# Open_IR_Blaster.net
KiCad netlist of a schematic drawn in EAGLE
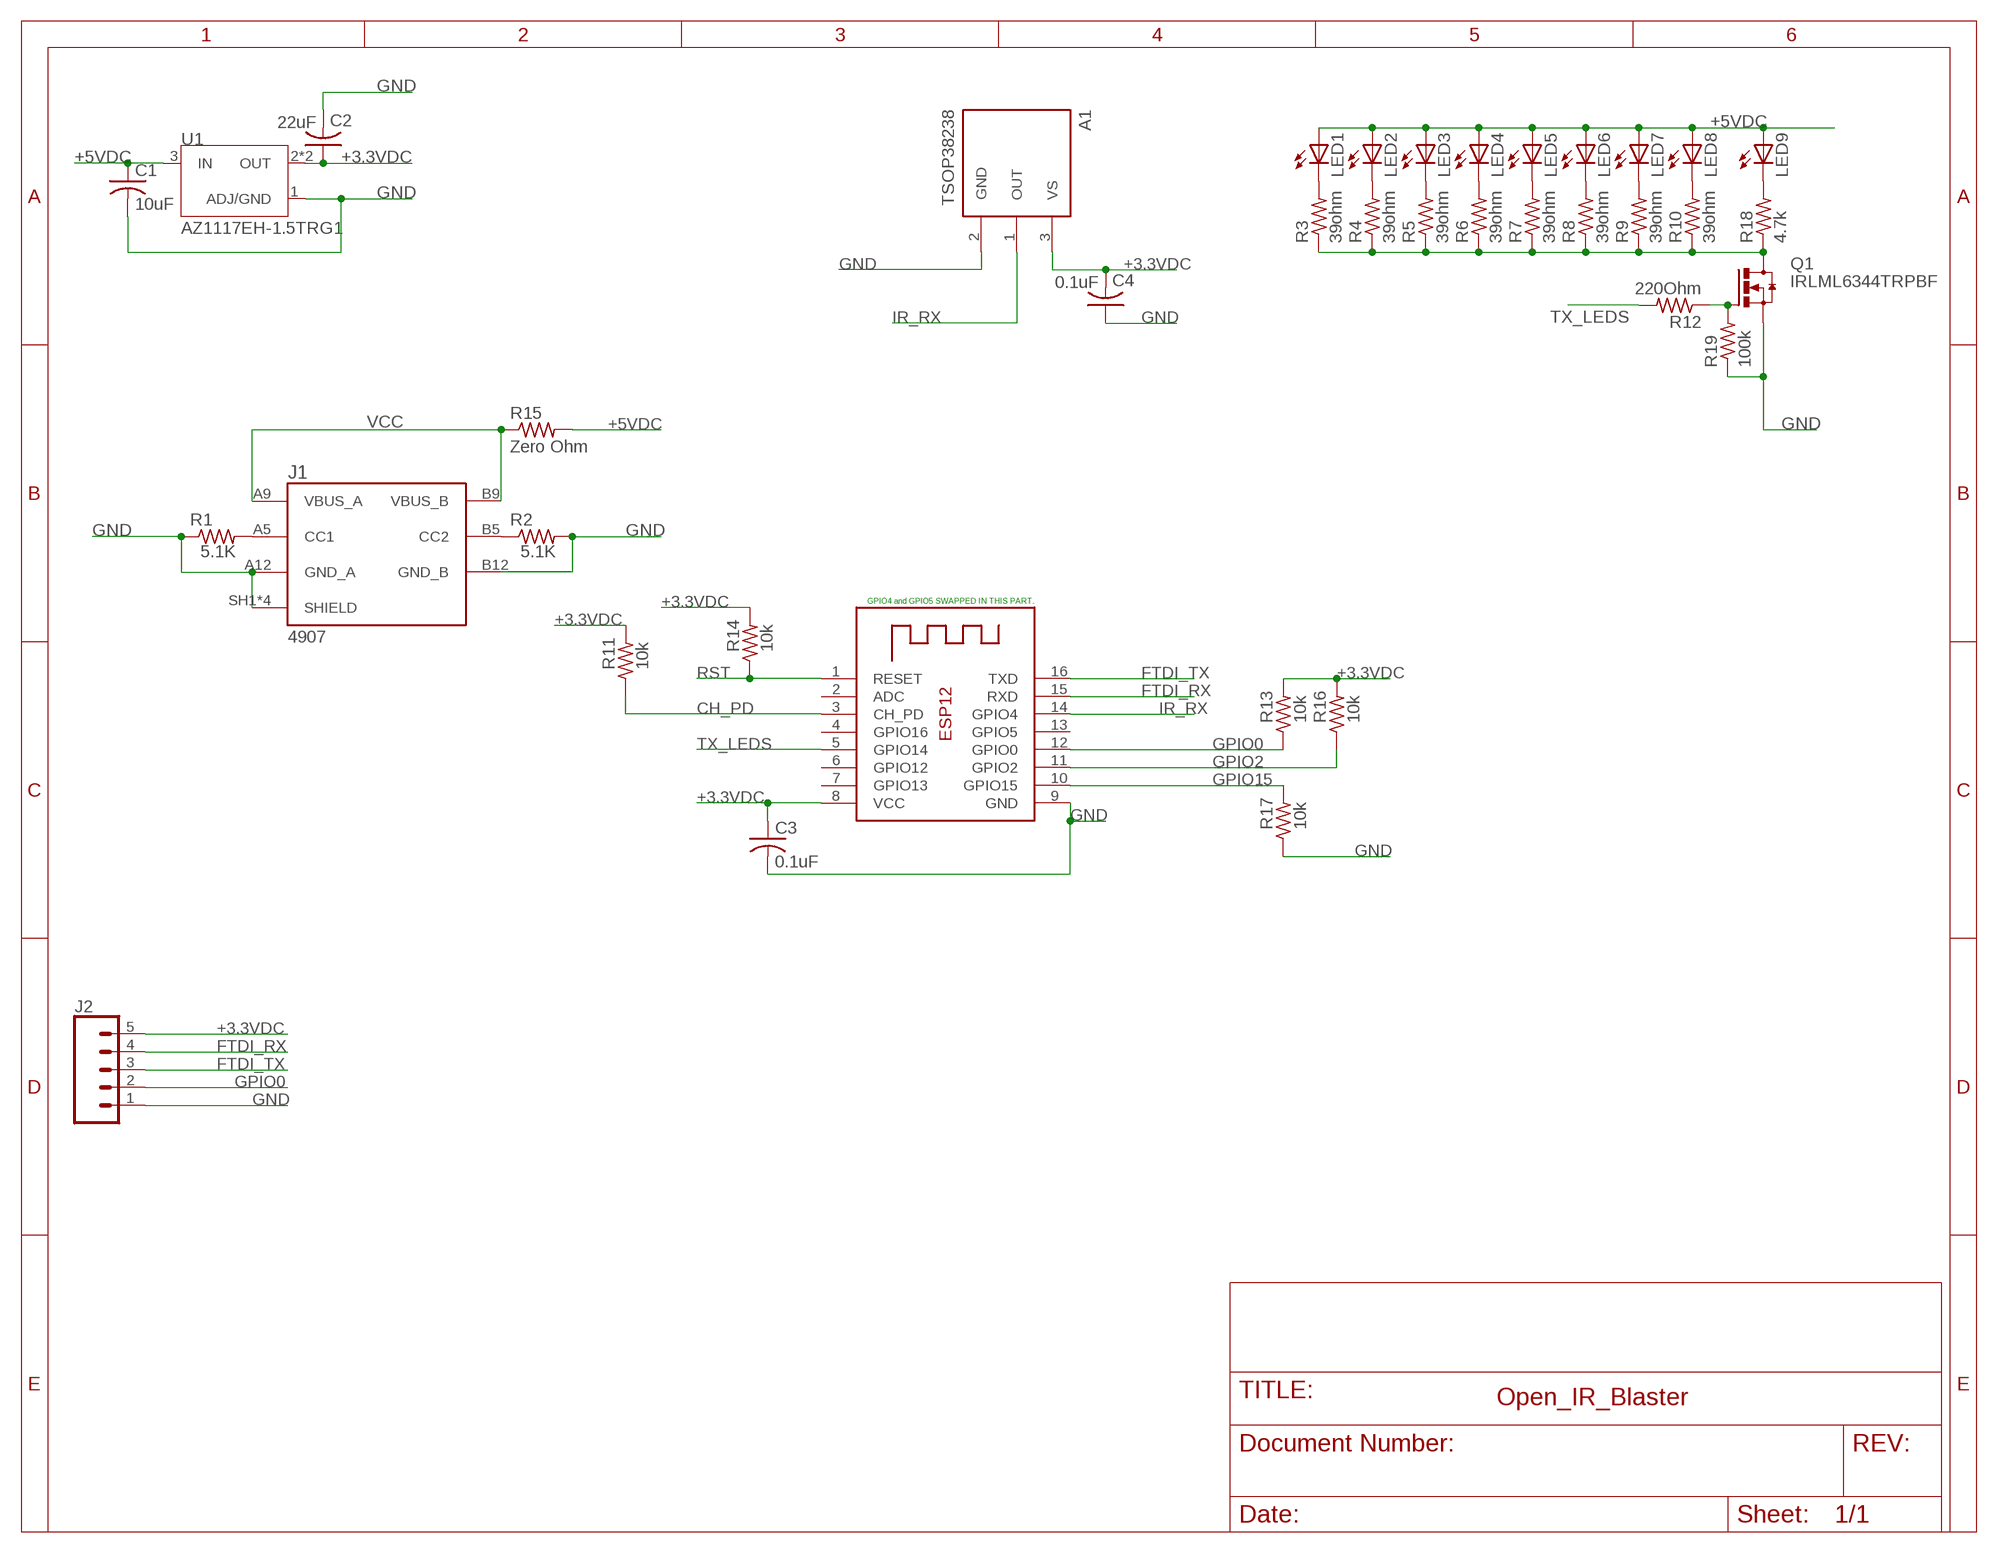
[diagram p0: schematic, sheet 1]

(export (version "E")
  (design (tool "Eeschema 10.0.6"))
  (components
    (comp (ref "A1")
      (value "TSOP38238")
      (footprint "eagle-import:XDCR_TSOP38238")
      (fields (field (name "DIGIKEY_PART_NUMBER") "751-1227-ND") (field (name "MF") "Vishay"))
      (libsource (lib "eagle-import") (part "TSOP38238"))
    )
    (comp (ref "C1")
      (value "10uF")
      (footprint "eagle-import:C0805")
      (libsource (lib "eagle-import") (part "C-USC0805"))
    )
    (comp (ref "C2")
      (value "22uF")
      (footprint "eagle-import:C0805")
      (libsource (lib "eagle-import") (part "C-USC0805"))
    )
    (comp (ref "C3")
      (value "0.1uF")
      (footprint "eagle-import:C0805")
      (libsource (lib "eagle-import") (part "C-USC0805"))
    )
    (comp (ref "C4")
      (value "0.1uF")
      (footprint "eagle-import:C0805")
      (libsource (lib "eagle-import") (part "C-USC0805"))
    )
    (comp (ref "J1")
      (value "4907")
      (footprint "eagle-import:ADAFRUIT_4907")
      (fields (field (name "MF") "Adafruit Industries LLC"))
      (libsource (lib "eagle-import") (part "4907"))
    )
    (comp (ref "J2")
      (value "CONN_05PTH_LONGPADS")
      (footprint "eagle-import:1X05_LONGPADS")
      (libsource (lib "eagle-import") (part "CONN_05PTH_LONGPADS"))
    )
    (comp (ref "LED1")
      (value "LED5MM")
      (footprint "eagle-import:LED5MM")
      (libsource (lib "eagle-import") (part "LED5MM"))
    )
    (comp (ref "LED2")
      (value "LED5MM")
      (footprint "eagle-import:LED5MM")
      (libsource (lib "eagle-import") (part "LED5MM"))
    )
    (comp (ref "LED3")
      (value "LED5MM")
      (footprint "eagle-import:LED5MM")
      (libsource (lib "eagle-import") (part "LED5MM"))
    )
    (comp (ref "LED4")
      (value "LED5MM")
      (footprint "eagle-import:LED5MM")
      (libsource (lib "eagle-import") (part "LED5MM"))
    )
    (comp (ref "LED5")
      (value "LED5MM")
      (footprint "eagle-import:LED5MM")
      (libsource (lib "eagle-import") (part "LED5MM"))
    )
    (comp (ref "LED6")
      (value "LED5MM")
      (footprint "eagle-import:LED5MM")
      (libsource (lib "eagle-import") (part "LED5MM"))
    )
    (comp (ref "LED7")
      (value "LED5MM")
      (footprint "eagle-import:LED5MM")
      (libsource (lib "eagle-import") (part "LED5MM"))
    )
    (comp (ref "LED8")
      (value "LED5MM")
      (footprint "eagle-import:LED5MM")
      (libsource (lib "eagle-import") (part "LED5MM"))
    )
    (comp (ref "LED9")
      (value "LEDCHIP-LED0603")
      (footprint "eagle-import:CHIP-LED0603")
      (libsource (lib "eagle-import") (part "LEDCHIP-LED0603"))
    )
    (comp (ref "Q1")
      (value "IRLML6344TRPBF")
      (footprint "eagle-import:SOT23")
      (fields
        (field (name "DIGIKEY_PART_NUMBER") "IRLML6344TRPBFTR-ND")
        (field (name "MF") "Infineon Technologies")
      )
      (libsource (lib "eagle-import") (part "IRLML6344TRPBF"))
    )
    (comp (ref "R1")
      (value "5.1K")
      (footprint "eagle-import:M0805")
      (libsource (lib "eagle-import") (part "R-US_M0805"))
    )
    (comp (ref "R2")
      (value "5.1K")
      (footprint "eagle-import:M0805")
      (libsource (lib "eagle-import") (part "R-US_M0805"))
    )
    (comp (ref "R3")
      (value "39ohm")
      (footprint "eagle-import:R1210")
      (libsource (lib "eagle-import") (part "R-US_R1210"))
    )
    (comp (ref "R4")
      (value "39ohm")
      (footprint "eagle-import:R1210")
      (libsource (lib "eagle-import") (part "R-US_R1210"))
    )
    (comp (ref "R5")
      (value "39ohm")
      (footprint "eagle-import:R1210")
      (libsource (lib "eagle-import") (part "R-US_R1210"))
    )
    (comp (ref "R6")
      (value "39ohm")
      (footprint "eagle-import:R1210")
      (libsource (lib "eagle-import") (part "R-US_R1210"))
    )
    (comp (ref "R7")
      (value "39ohm")
      (footprint "eagle-import:R1210")
      (libsource (lib "eagle-import") (part "R-US_R1210"))
    )
    (comp (ref "R8")
      (value "39ohm")
      (footprint "eagle-import:R1210")
      (libsource (lib "eagle-import") (part "R-US_R1210"))
    )
    (comp (ref "R9")
      (value "39ohm")
      (footprint "eagle-import:R1210")
      (libsource (lib "eagle-import") (part "R-US_R1210"))
    )
    (comp (ref "R10")
      (value "39ohm")
      (footprint "eagle-import:R1210")
      (libsource (lib "eagle-import") (part "R-US_R1210"))
    )
    (comp (ref "R11")
      (value "10k")
      (footprint "eagle-import:M0805")
      (libsource (lib "eagle-import") (part "R-US_M0805"))
    )
    (comp (ref "R12")
      (value "220Ohm")
      (footprint "eagle-import:M0805")
      (libsource (lib "eagle-import") (part "R-US_M0805"))
    )
    (comp (ref "R13")
      (value "10k")
      (footprint "eagle-import:M0805")
      (libsource (lib "eagle-import") (part "R-US_M0805"))
    )
    (comp (ref "R14")
      (value "10k")
      (footprint "eagle-import:M0805")
      (libsource (lib "eagle-import") (part "R-US_M0805"))
    )
    (comp (ref "R15")
      (value "Zero Ohm")
      (footprint "eagle-import:R1210")
      (libsource (lib "eagle-import") (part "adafruit_420_R-US_R1210"))
    )
    (comp (ref "R16")
      (value "10k")
      (footprint "eagle-import:M0805")
      (libsource (lib "eagle-import") (part "R-US_M0805"))
    )
    (comp (ref "R17")
      (value "10k")
      (footprint "eagle-import:M0805")
      (libsource (lib "eagle-import") (part "R-US_M0805"))
    )
    (comp (ref "R18")
      (value "4.7k")
      (footprint "eagle-import:R0603")
      (libsource (lib "eagle-import") (part "adafruit_420_R-US_R0603"))
    )
    (comp (ref "R19")
      (value "100k")
      (footprint "eagle-import:R0603")
      (libsource (lib "eagle-import") (part "adafruit_420_R-US_R0603"))
    )
    (comp (ref "U1")
      (value "AZ1117EH-1.5TRG1")
      (footprint "eagle-import:SOT230P700X180-4N")
      (fields (field (name "MF") "Diodes Inc."))
      (libsource (lib "eagle-import") (part "AZ1117EH-1.5TRG1"))
    )
    (comp (ref "X1")
      (value "ESP-12")
      (footprint "eagle-import:ESP-12")
      (libsource (lib "eagle-import") (part "ESP-12"))
    )
  )
  (nets
    (net (code "1") (name "/+3.3VDC") (class "Default")
      (node (ref "A1") (pin "3") (pinfunction "VS_3") (pintype "power_in"))
      (node (ref "C2") (pin "1") (pinfunction "1_1") (pintype "passive"))
      (node (ref "C3") (pin "1") (pinfunction "1_1") (pintype "passive"))
      (node (ref "C4") (pin "2") (pinfunction "2_2") (pintype "passive"))
      (node (ref "J2") (pin "5") (pinfunction "5_5") (pintype "passive"))
      (node (ref "R11") (pin "2") (pinfunction "2_2") (pintype "passive"))
      (node (ref "R13") (pin "2") (pinfunction "2_2") (pintype "passive"))
      (node (ref "R14") (pin "2") (pinfunction "2_2") (pintype "passive"))
      (node (ref "R16") (pin "2") (pinfunction "2_2") (pintype "passive"))
      (node (ref "U1") (pin "2") (pinfunction "OUT_2") (pintype "output"))
      (node (ref "U1") (pin "4") (pinfunction "OUT_4") (pintype "output"))
      (node (ref "X1") (pin "8") (pinfunction "VCC_8") (pintype "power_in"))
    )
    (net (code "2") (name "/+5VDC") (class "Default")
      (node (ref "C1") (pin "1") (pinfunction "1_1") (pintype "passive"))
      (node (ref "LED1") (pin "A") (pinfunction "A_A") (pintype "passive"))
      (node (ref "LED2") (pin "A") (pinfunction "A_A") (pintype "passive"))
      (node (ref "LED3") (pin "A") (pinfunction "A_A") (pintype "passive"))
      (node (ref "LED4") (pin "A") (pinfunction "A_A") (pintype "passive"))
      (node (ref "LED5") (pin "A") (pinfunction "A_A") (pintype "passive"))
      (node (ref "LED6") (pin "A") (pinfunction "A_A") (pintype "passive"))
      (node (ref "LED7") (pin "A") (pinfunction "A_A") (pintype "passive"))
      (node (ref "LED8") (pin "A") (pinfunction "A_A") (pintype "passive"))
      (node (ref "LED9") (pin "A") (pinfunction "A_A") (pintype "passive"))
      (node (ref "R15") (pin "2") (pinfunction "2_2") (pintype "passive"))
      (node (ref "U1") (pin "3") (pinfunction "IN_3") (pintype "input"))
    )
    (net (code "3") (name "/CH_PD") (class "Default")
      (node (ref "R11") (pin "1") (pinfunction "1_1") (pintype "passive"))
      (node (ref "X1") (pin "3") (pinfunction "CH_PD_3") (pintype "input"))
    )
    (net (code "4") (name "/FTDI_RX") (class "Default")
      (node (ref "J2") (pin "4") (pinfunction "4_4") (pintype "passive"))
      (node (ref "X1") (pin "15") (pinfunction "RXD_15") (pintype "input"))
    )
    (net (code "5") (name "/FTDI_TX") (class "Default")
      (node (ref "J2") (pin "3") (pinfunction "3_3") (pintype "passive"))
      (node (ref "X1") (pin "16") (pinfunction "TXD_16") (pintype "output"))
    )
    (net (code "6") (name "/GND") (class "Default")
      (node (ref "A1") (pin "2") (pinfunction "GND_2") (pintype "power_in"))
      (node (ref "C1") (pin "2") (pinfunction "2_2") (pintype "passive"))
      (node (ref "C2") (pin "2") (pinfunction "2_2") (pintype "passive"))
      (node (ref "C3") (pin "2") (pinfunction "2_2") (pintype "passive"))
      (node (ref "C4") (pin "1") (pinfunction "1_1") (pintype "passive"))
      (node (ref "J1") (pin "A12") (pinfunction "GND_A_A12") (pintype "power_in"))
      (node (ref "J1") (pin "B12") (pinfunction "GND_B_B12") (pintype "power_in"))
      (node (ref "J1") (pin "SH1") (pinfunction "SHIELD_SH1") (pintype "passive"))
      (node (ref "J1") (pin "SH2") (pinfunction "SHIELD_SH2") (pintype "passive"))
      (node (ref "J1") (pin "SH3") (pinfunction "SHIELD_SH3") (pintype "passive"))
      (node (ref "J1") (pin "SH4") (pinfunction "SHIELD_SH4") (pintype "passive"))
      (node (ref "J2") (pin "1") (pinfunction "1_1") (pintype "passive"))
      (node (ref "Q1") (pin "2") (pinfunction "S_2") (pintype "passive"))
      (node (ref "R1") (pin "1") (pinfunction "1_1") (pintype "passive"))
      (node (ref "R17") (pin "1") (pinfunction "1_1") (pintype "passive"))
      (node (ref "R19") (pin "1") (pinfunction "1_1") (pintype "passive"))
      (node (ref "R2") (pin "2") (pinfunction "2_2") (pintype "passive"))
      (node (ref "U1") (pin "1") (pinfunction "ADJ/GND_1") (pintype "power_in"))
      (node (ref "X1") (pin "9") (pinfunction "GND_9") (pintype "power_in"))
    )
    (net (code "7") (name "/GPIO0") (class "Default")
      (node (ref "J2") (pin "2") (pinfunction "2_2") (pintype "passive"))
      (node (ref "R13") (pin "1") (pinfunction "1_1") (pintype "passive"))
      (node (ref "X1") (pin "12") (pinfunction "GPIO0_12") (pintype "bidirectional"))
    )
    (net (code "8") (name "/GPIO2") (class "Default")
      (node (ref "R16") (pin "1") (pinfunction "1_1") (pintype "passive"))
      (node (ref "X1") (pin "11") (pinfunction "GPIO2_11") (pintype "bidirectional"))
    )
    (net (code "9") (name "/GPIO15") (class "Default")
      (node (ref "R17") (pin "2") (pinfunction "2_2") (pintype "passive"))
      (node (ref "X1") (pin "10") (pinfunction "GPIO15_10") (pintype "bidirectional"))
    )
    (net (code "10") (name "/IR_RX") (class "Default")
      (node (ref "A1") (pin "1") (pinfunction "OUT_1") (pintype "output"))
      (node (ref "X1") (pin "14") (pinfunction "GPIO4_14") (pintype "bidirectional"))
    )
    (net (code "11") (name "/RST") (class "Default")
      (node (ref "R14") (pin "1") (pinfunction "1_1") (pintype "passive"))
      (node (ref "X1") (pin "1") (pinfunction "RESET_1") (pintype "input"))
    )
    (net (code "12") (name "/TX_LEDS") (class "Default")
      (node (ref "R12") (pin "2") (pinfunction "2_2") (pintype "passive"))
      (node (ref "X1") (pin "5") (pinfunction "GPIO14_5") (pintype "bidirectional"))
    )
    (net (code "13") (name "/VCC") (class "Default")
      (node (ref "J1") (pin "A9") (pinfunction "VBUS_A_A9") (pintype "power_in"))
      (node (ref "J1") (pin "B9") (pinfunction "VBUS_B_B9") (pintype "power_in"))
      (node (ref "R15") (pin "1") (pinfunction "1_1") (pintype "passive"))
    )
    (net (code "14") (name "Net-(J1-CC1)") (class "Default")
      (node (ref "J1") (pin "A5") (pinfunction "CC1_A5") (pintype "bidirectional"))
      (node (ref "R1") (pin "2") (pinfunction "2_2") (pintype "passive"))
    )
    (net (code "15") (name "Net-(J1-CC2)") (class "Default")
      (node (ref "J1") (pin "B5") (pinfunction "CC2_B5") (pintype "bidirectional"))
      (node (ref "R2") (pin "1") (pinfunction "1_1") (pintype "passive"))
    )
    (net (code "16") (name "Net-(LED1-C)") (class "Default")
      (node (ref "LED1") (pin "K") (pinfunction "C_K") (pintype "passive"))
      (node (ref "R3") (pin "2") (pinfunction "2_2") (pintype "passive"))
    )
    (net (code "17") (name "Net-(LED2-C)") (class "Default")
      (node (ref "LED2") (pin "K") (pinfunction "C_K") (pintype "passive"))
      (node (ref "R4") (pin "2") (pinfunction "2_2") (pintype "passive"))
    )
    (net (code "18") (name "Net-(LED3-C)") (class "Default")
      (node (ref "LED3") (pin "K") (pinfunction "C_K") (pintype "passive"))
      (node (ref "R5") (pin "2") (pinfunction "2_2") (pintype "passive"))
    )
    (net (code "19") (name "Net-(LED4-C)") (class "Default")
      (node (ref "LED4") (pin "K") (pinfunction "C_K") (pintype "passive"))
      (node (ref "R6") (pin "2") (pinfunction "2_2") (pintype "passive"))
    )
    (net (code "20") (name "Net-(LED5-C)") (class "Default")
      (node (ref "LED5") (pin "K") (pinfunction "C_K") (pintype "passive"))
      (node (ref "R7") (pin "2") (pinfunction "2_2") (pintype "passive"))
    )
    (net (code "21") (name "Net-(LED6-C)") (class "Default")
      (node (ref "LED6") (pin "K") (pinfunction "C_K") (pintype "passive"))
      (node (ref "R8") (pin "2") (pinfunction "2_2") (pintype "passive"))
    )
    (net (code "22") (name "Net-(LED7-C)") (class "Default")
      (node (ref "LED7") (pin "K") (pinfunction "C_K") (pintype "passive"))
      (node (ref "R9") (pin "2") (pinfunction "2_2") (pintype "passive"))
    )
    (net (code "23") (name "Net-(LED8-C)") (class "Default")
      (node (ref "LED8") (pin "K") (pinfunction "C_K") (pintype "passive"))
      (node (ref "R10") (pin "2") (pinfunction "2_2") (pintype "passive"))
    )
    (net (code "24") (name "Net-(LED9-PadC)") (class "Default")
      (node (ref "LED9") (pin "C") (pinfunction "C_C") (pintype "passive"))
      (node (ref "R18") (pin "2") (pinfunction "2_2") (pintype "passive"))
    )
    (net (code "25") (name "Net-(Q1-D)") (class "Default")
      (node (ref "Q1") (pin "3") (pinfunction "D_3") (pintype "passive"))
      (node (ref "R10") (pin "1") (pinfunction "1_1") (pintype "passive"))
      (node (ref "R18") (pin "1") (pinfunction "1_1") (pintype "passive"))
      (node (ref "R3") (pin "1") (pinfunction "1_1") (pintype "passive"))
      (node (ref "R4") (pin "1") (pinfunction "1_1") (pintype "passive"))
      (node (ref "R5") (pin "1") (pinfunction "1_1") (pintype "passive"))
      (node (ref "R6") (pin "1") (pinfunction "1_1") (pintype "passive"))
      (node (ref "R7") (pin "1") (pinfunction "1_1") (pintype "passive"))
      (node (ref "R8") (pin "1") (pinfunction "1_1") (pintype "passive"))
      (node (ref "R9") (pin "1") (pinfunction "1_1") (pintype "passive"))
    )
    (net (code "26") (name "Net-(Q1-G)") (class "Default")
      (node (ref "Q1") (pin "1") (pinfunction "G_1") (pintype "passive"))
      (node (ref "R12") (pin "1") (pinfunction "1_1") (pintype "passive"))
      (node (ref "R19") (pin "2") (pinfunction "2_2") (pintype "passive"))
    )
    (net (code "27") (name "unconnected-(X1-ADC-Pad2)") (class "Default")
      (node (ref "X1") (pin "2") (pinfunction "ADC_2") (pintype "passive"))
    )
    (net (code "28") (name "unconnected-(X1-GPIO5-Pad13)") (class "Default")
      (node (ref "X1") (pin "13") (pinfunction "GPIO5_13") (pintype "bidirectional"))
    )
    (net (code "29") (name "unconnected-(X1-GPIO12-Pad6)") (class "Default")
      (node (ref "X1") (pin "6") (pinfunction "GPIO12_6") (pintype "bidirectional"))
    )
    (net (code "30") (name "unconnected-(X1-GPIO13-Pad7)") (class "Default")
      (node (ref "X1") (pin "7") (pinfunction "GPIO13_7") (pintype "bidirectional"))
    )
    (net (code "31") (name "unconnected-(X1-GPIO16-Pad4)") (class "Default")
      (node (ref "X1") (pin "4") (pinfunction "GPIO16_4") (pintype "bidirectional"))
    )
  )
)
